# USB_to_UART.net
KiCad netlist of a schematic drawn in Altium Designer
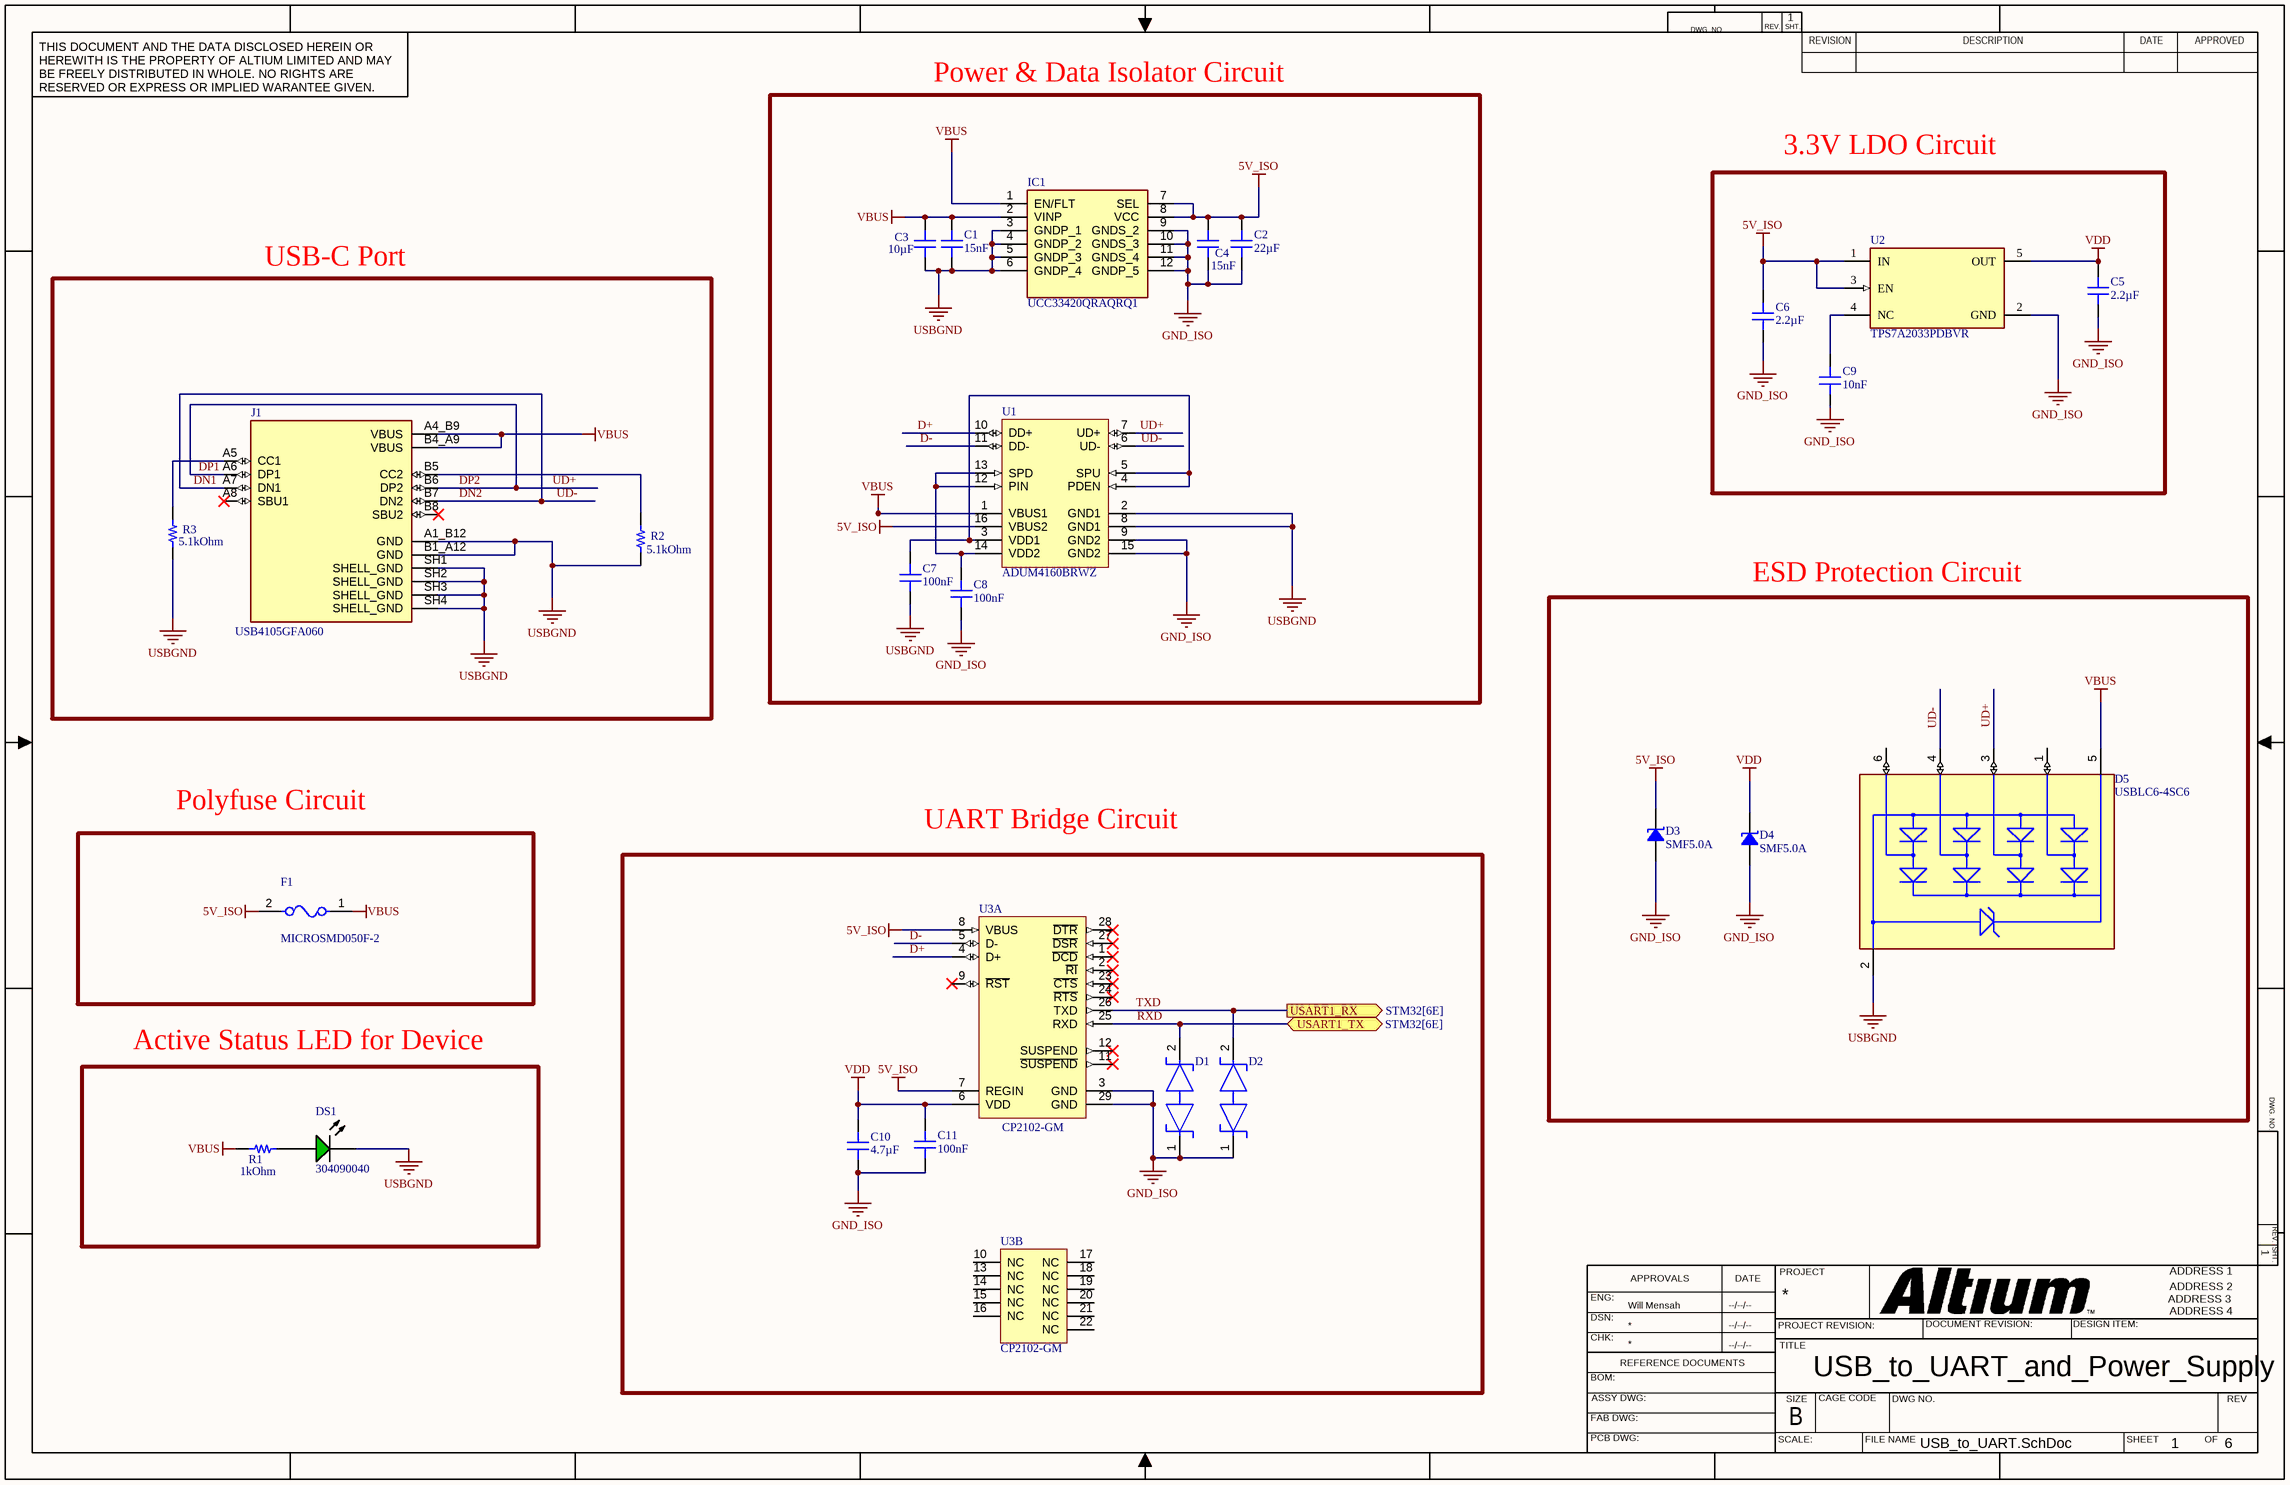
[diagram p0: USB_to_UART.SchDoc]

(export (version "E")
  (design (tool "Eeschema 10.0.6"))
  (components
    (comp (ref "C1")
      (value "15nF")
      (footprint "CAP 1206_3216 - 0.8MM")
      (description "CAP CER 15000PF 630V X7R 1206")
      (fields (field (name "PART NUMBER") "885342208013"))
      (libsource (lib "University of Massachusetts Lowell") (part "CAPACITOR"))
    )
    (comp (ref "C2")
      (value "22µF")
      (footprint "MURATA - GRM32E")
      (description "CAP CER 22UF 25V X7R 1210")
      (fields (field (name "PART NUMBER") "GRM32ER71E226ME15L"))
      (libsource (lib "University of Massachusetts Lowell") (part "CAPACITOR"))
    )
    (comp (ref "C3")
      (value "10µF")
      (footprint "MURATA - GRM32E")
      (description "CAP CER 10UF 50V X7R 1210")
      (fields (field (name "PART NUMBER") "GRM32ER71H106MA12L"))
      (libsource (lib "University of Massachusetts Lowell") (part "CAPACITOR"))
    )
    (comp (ref "C4")
      (value "15nF")
      (footprint "CAP 1206_3216 - 0.8MM")
      (description "CAP CER 15000PF 630V X7R 1206")
      (fields (field (name "PART NUMBER") "885342208013"))
      (libsource (lib "University of Massachusetts Lowell") (part "CAPACITOR"))
    )
    (comp (ref "C5")
      (value "2.2µF")
      (footprint "MURATA CAP GCM31M 1206_3216")
      (description "CAP CER 2.2UF 100V X8L 1206")
      (fields (field (name "PART NUMBER") "GCM31CL8EL225KE07L"))
      (libsource (lib "University of Massachusetts Lowell") (part "CAPACITOR"))
    )
    (comp (ref "C6")
      (value "2.2µF")
      (footprint "MURATA CAP GCM31M 1206_3216")
      (description "CAP CER 2.2UF 100V X8L 1206")
      (fields (field (name "PART NUMBER") "GCM31CL8EL225KE07L"))
      (libsource (lib "University of Massachusetts Lowell") (part "CAPACITOR"))
    )
    (comp (ref "C7")
      (value "100nF")
      (footprint "MURATA CAP GCM31M 1206_3216")
      (description "CAP CER 0.1UF 50V C0G/NP0 1206")
      (fields (field (name "PART NUMBER") "GCM31C5C1H104FA16L"))
      (libsource (lib "University of Massachusetts Lowell") (part "CAPACITOR"))
    )
    (comp (ref "C8")
      (value "100nF")
      (footprint "MURATA CAP GCM31M 1206_3216")
      (description "CAP CER 0.1UF 50V C0G/NP0 1206")
      (fields (field (name "PART NUMBER") "GCM31C5C1H104FA16L"))
      (libsource (lib "University of Massachusetts Lowell") (part "CAPACITOR"))
    )
    (comp (ref "C9")
      (value "10nF")
      (footprint "MURATA CAP GRM31B 1206_3216")
      (description "CAP CER 10000PF 250V U2J 1206")
      (fields (field (name "PART NUMBER") "GRM31B7U2E103JW31L"))
      (libsource (lib "University of Massachusetts Lowell") (part "CAPACITOR"))
    )
    (comp (ref "C10")
      (value "4.7µF")
      (footprint "MURATA GRM21B 0805_2012")
      (description "CAP CER 4.7UF 10V X7R 0805")
      (fields (field (name "PART NUMBER") "GRM21BR71A475KE51L"))
      (libsource (lib "University of Massachusetts Lowell") (part "CAPACITOR"))
    )
    (comp (ref "C11")
      (value "100nF")
      (footprint "MURATA CAP GCM31M 1206_3216")
      (description "CAP CER 0.1UF 50V C0G/NP0 1206")
      (fields (field (name "PART NUMBER") "GCM31C5C1H104FA16L"))
      (libsource (lib "University of Massachusetts Lowell") (part "CAPACITOR"))
    )
    (comp (ref "D1")
      (value "TPD1E10B06DPYR")
      (footprint "FP-DPY0002A-MFG")
      (description "TVS DIODE 5.5V 14V 2X1SON")
      (fields (field (name "MANUFACTURER") "Texas Instruments"))
      (libsource (lib "Altium Content Vault") (part "208e19b57522434895fa003e5d5b197"))
    )
    (comp (ref "D2")
      (value "TPD1E10B06DPYR")
      (footprint "FP-DPY0002A-MFG")
      (description "TVS DIODE 5.5V 14V 2X1SON")
      (fields (field (name "MANUFACTURER") "Texas Instruments"))
      (libsource (lib "Altium Content Vault") (part "208e19b57522434895fa003e5d5b197"))
    )
    (comp (ref "D3")
      (value "SMF5.0A")
      (footprint "SOD123F")
      (description "TVS SOD123FL 5V 200W UNIDIR")
      (libsource (lib "University of Massachusetts Lowell") (part "DIODE TVS UNI"))
    )
    (comp (ref "D4")
      (value "SMF5.0A")
      (footprint "SOD123F")
      (description "TVS SOD123FL 5V 200W UNIDIR")
      (libsource (lib "University of Massachusetts Lowell") (part "DIODE TVS UNI"))
    )
    (comp (ref "D5")
      (value "USBLC6-4SC6")
      (footprint "FP-SOT23-6L-MFG")
      (description "TVS DIODE 5.25V 17V SOT23-6")
      (fields
        (field (name "MANUFACTURER") "STMicroelectronics")
        (field (name "OCTOPART") "https://octopart.com/usblc6-4sc6-stmicroelectronics-347147")
      )
      (libsource (lib "Altium Content Vault") (part "3e70b616ccdc4c88b528e1820c4a7da"))
    )
    (comp (ref "DS1")
      (value "304090040")
      (footprint "LED-2P-2.28-3MM")
      (description "Green LED, 80 mW, 20 mA, -25 to 85 degC, 2-Pin THD")
      (fields (field (name "MANUFACTURER") "Shenzhen CGX"))
      (libsource (lib "University of Massachusetts Lowell") (part "LED-GREEN-AK-2"))
    )
    (comp (ref "F1")
      (value "MICROSMD050F-2")
      (footprint "FP-microSMD-MFG")
      (description "PTC RESET FUSE 13.2V 500MA 1210")
      (fields
        (field (name "MANUFACTURER") "Littelfuse")
        (field (name "OCTOPART") "https://octopart.com/microsmd050f-2-littelfuse-74214982")
      )
      (libsource (lib "Altium Content Vault") (part "5bcf9b9f640e542cf0359d10258e979"))
    )
    (comp (ref "IC1")
      (value "UCC33420QRAQRQ1")
      (footprint "SamacSys:UCC33020QRAQRQ1")
      (description "Integrated Circuit")
      (fields (field (name "MOUSER PART NUMBER") "595-UCC33420QRAQRQ1"))
      (libsource (lib "*") (part "UCC33420QRAQRQ1"))
    )
    (comp (ref "J1")
      (value "USB4105GFA060")
      (footprint "GCT_USB4105GFA060")
      (fields (field (name "MF") "Global Connector Technology"))
      (libsource (lib "University of Massachusetts Lowell") (part "USB4105GFA060"))
    )
    (comp (ref "R1")
      (value "1kOhm")
      (footprint "YAGEO RES 1206_3216")
      (description "RES 1K OHM 1% 1/4W 1206")
      (fields (field (name "PART NUMBER") "RC1206FR-101KL"))
      (libsource (lib "University of Massachusetts Lowell") (part "RESISTOR"))
    )
    (comp (ref "R2")
      (value "5.1kOhm")
      (footprint "YAGEO RES 1206_3216")
      (description "RES 5.1K OHM 0.1% 1/4W 1206")
      (fields (field (name "PART NUMBER") "RP1206BRD075K1L"))
      (libsource (lib "University of Massachusetts Lowell") (part "RESISTOR"))
    )
    (comp (ref "R3")
      (value "5.1kOhm")
      (footprint "YAGEO RES 1206_3216")
      (description "RES 5.1K OHM 0.1% 1/4W 1206")
      (fields (field (name "PART NUMBER") "RP1206BRD075K1L"))
      (libsource (lib "University of Massachusetts Lowell") (part "RESISTOR"))
    )
    (comp (ref "U1")
      (value "ADUM4160BRWZ")
      (footprint "RW-16_L")
      (fields (field (name "MANUFACTURER") "Analog Devices"))
      (libsource (lib "Altium Content Vault") (part "ADI-ADUM4160-16"))
    )
    (comp (ref "U2")
      (value "TPS7A2033PDBVR")
      (footprint "FP-DBV0005A-MFG")
      (description "IC REG LINEAR 3.3V 300MA SOT23-5")
      (libsource (lib "Altium Content Vault") (part "76aa7ad0ceb1012e0d85aeafc53095f"))
    )
    (comp (ref "U3")
      (value "CP2102-GM")
      (footprint "SLAB-QFN-28-3125x3125TP_N")
      (description "Single-Chip USB to UART Bridge, 1024 Bytes EEPROM, -40 to 85 degC, 28-pin QFN, Tube")
      (fields (field (name "MANUFACTURER") "Silicon Labs"))
      (libsource (lib "Altium Content Vault") (part "SLAB-CP210X-QFN-28-29"))
    )
  )
  (nets
    (net (code "1") (name "/D+") (class "Default")
      (node (ref "U1") (pin "10") (pinfunction "DD+_10") (pintype "bidirectional"))
      (node (ref "U3") (pin "4") (pinfunction "D+_4") (pintype "bidirectional"))
    )
    (net (code "2") (name "/D-") (class "Default")
      (node (ref "U1") (pin "11") (pinfunction "DD-_11") (pintype "bidirectional"))
      (node (ref "U3") (pin "5") (pinfunction "D-_5") (pintype "bidirectional"))
    )
    (net (code "3") (name "/DN1") (class "Default")
      (node (ref "D5") (pin "4") (pinfunction "I/O3_4") (pintype "bidirectional"))
      (node (ref "J1") (pin "A7") (pinfunction "DN1_A7") (pintype "bidirectional"))
      (node (ref "J1") (pin "B7") (pinfunction "DN2_B7") (pintype "bidirectional"))
      (node (ref "U1") (pin "6") (pinfunction "UD-_6") (pintype "bidirectional"))
    )
    (net (code "4") (name "/DP1") (class "Default")
      (node (ref "D5") (pin "3") (pinfunction "I/O2_3") (pintype "bidirectional"))
      (node (ref "J1") (pin "A6") (pinfunction "DP1_A6") (pintype "bidirectional"))
      (node (ref "J1") (pin "B6") (pinfunction "DP2_B6") (pintype "bidirectional"))
      (node (ref "U1") (pin "7") (pinfunction "UD+_7") (pintype "bidirectional"))
    )
    (net (code "5") (name "/RXD") (class "Default")
      (node (ref "D1") (pin "2") (pinfunction "2_2") (pintype "passive"))
      (node (ref "U3") (pin "25") (pinfunction "RXD_25") (pintype "input"))
    )
    (net (code "6") (name "/TXD") (class "Default")
      (node (ref "D2") (pin "2") (pinfunction "2_2") (pintype "passive"))
      (node (ref "U3") (pin "26") (pinfunction "TXD_26") (pintype "output"))
    )
    (net (code "7") (name "5V_ISO") (class "Default")
      (node (ref "C2") (pin "2") (pinfunction "2_2") (pintype "passive"))
      (node (ref "C4") (pin "2") (pinfunction "2_2") (pintype "passive"))
      (node (ref "C6") (pin "2") (pinfunction "2_2") (pintype "passive"))
      (node (ref "D3") (pin "2") (pinfunction "2_2") (pintype "passive"))
      (node (ref "F1") (pin "2") (pinfunction "2_2") (pintype "passive"))
      (node (ref "IC1") (pin "7") (pinfunction "SEL_7") (pintype "passive"))
      (node (ref "IC1") (pin "8") (pinfunction "VCC_8") (pintype "passive"))
      (node (ref "U1") (pin "16") (pinfunction "VBUS2_16") (pintype "power_in"))
      (node (ref "U2") (pin "1") (pinfunction "IN_1") (pintype "power_in"))
      (node (ref "U2") (pin "3") (pinfunction "EN_3") (pintype "input"))
      (node (ref "U3") (pin "7") (pinfunction "REGIN_7") (pintype "power_in"))
      (node (ref "U3") (pin "8") (pinfunction "VBUS_8") (pintype "input"))
    )
    (net (code "8") (name "GND_ISO") (class "Default")
      (node (ref "C10") (pin "1") (pinfunction "1_1") (pintype "passive"))
      (node (ref "C11") (pin "1") (pinfunction "1_1") (pintype "passive"))
      (node (ref "C2") (pin "1") (pinfunction "1_1") (pintype "passive"))
      (node (ref "C4") (pin "1") (pinfunction "1_1") (pintype "passive"))
      (node (ref "C5") (pin "1") (pinfunction "1_1") (pintype "passive"))
      (node (ref "C6") (pin "1") (pinfunction "1_1") (pintype "passive"))
      (node (ref "C8") (pin "1") (pinfunction "1_1") (pintype "passive"))
      (node (ref "C9") (pin "1") (pinfunction "1_1") (pintype "passive"))
      (node (ref "D1") (pin "1") (pinfunction "1_1") (pintype "passive"))
      (node (ref "D2") (pin "1") (pinfunction "1_1") (pintype "passive"))
      (node (ref "D3") (pin "1") (pinfunction "1_1") (pintype "passive"))
      (node (ref "D4") (pin "1") (pinfunction "1_1") (pintype "passive"))
      (node (ref "IC1") (pin "10") (pinfunction "GNDS_3_10") (pintype "passive"))
      (node (ref "IC1") (pin "11") (pinfunction "GNDS_4_11") (pintype "passive"))
      (node (ref "IC1") (pin "12") (pinfunction "GNDP_5_12") (pintype "passive"))
      (node (ref "IC1") (pin "9") (pinfunction "GNDS_2_9") (pintype "passive"))
      (node (ref "U1") (pin "15") (pinfunction "GND2_15") (pintype "power_in"))
      (node (ref "U1") (pin "9") (pinfunction "GND2_9") (pintype "power_in"))
      (node (ref "U2") (pin "2") (pinfunction "GND_2") (pintype "power_in"))
      (node (ref "U3") (pin "29") (pinfunction "GND_29") (pintype "power_in"))
      (node (ref "U3") (pin "3") (pinfunction "GND_3") (pintype "power_in"))
    )
    (net (code "9") (name "Net-(DS1-A)") (class "Default")
      (node (ref "DS1") (pin "1") (pinfunction "A_1") (pintype "passive"))
      (node (ref "R1") (pin "1") (pinfunction "1_1") (pintype "passive"))
    )
    (net (code "10") (name "Net-(J1-CC1)") (class "Default")
      (node (ref "J1") (pin "A5") (pinfunction "CC1_A5") (pintype "bidirectional"))
      (node (ref "R3") (pin "1") (pinfunction "1_1") (pintype "passive"))
    )
    (net (code "11") (name "Net-(J1-CC2)") (class "Default")
      (node (ref "J1") (pin "B5") (pinfunction "CC2_B5") (pintype "bidirectional"))
      (node (ref "R2") (pin "2") (pinfunction "2_2") (pintype "passive"))
    )
    (net (code "12") (name "Net-(U1-PDEN)") (class "Default")
      (node (ref "C7") (pin "2") (pinfunction "2_2") (pintype "passive"))
      (node (ref "U1") (pin "3") (pinfunction "VDD1_3") (pintype "power_in"))
      (node (ref "U1") (pin "4") (pinfunction "PDEN_4") (pintype "input"))
      (node (ref "U1") (pin "5") (pinfunction "SPU_5") (pintype "input"))
    )
    (net (code "13") (name "Net-(U1-PIN)") (class "Default")
      (node (ref "C8") (pin "2") (pinfunction "2_2") (pintype "passive"))
      (node (ref "U1") (pin "12") (pinfunction "PIN_12") (pintype "input"))
      (node (ref "U1") (pin "13") (pinfunction "SPD_13") (pintype "input"))
      (node (ref "U1") (pin "14") (pinfunction "VDD2_14") (pintype "power_in"))
    )
    (net (code "14") (name "Net-(U2-NC)") (class "Default")
      (node (ref "C9") (pin "2") (pinfunction "2_2") (pintype "passive"))
      (node (ref "U2") (pin "4") (pinfunction "NC_4") (pintype "passive"))
    )
    (net (code "15") (name "USBGND") (class "Default")
      (node (ref "C1") (pin "1") (pinfunction "1_1") (pintype "passive"))
      (node (ref "C3") (pin "1") (pinfunction "1_1") (pintype "passive"))
      (node (ref "C7") (pin "1") (pinfunction "1_1") (pintype "passive"))
      (node (ref "D5") (pin "2") (pinfunction "GND_2") (pintype "power_in"))
      (node (ref "DS1") (pin "2") (pinfunction "K_2") (pintype "passive"))
      (node (ref "IC1") (pin "3") (pinfunction "GNDP_1_3") (pintype "passive"))
      (node (ref "IC1") (pin "4") (pinfunction "GNDP_2_4") (pintype "passive"))
      (node (ref "IC1") (pin "5") (pinfunction "GNDP_3_5") (pintype "passive"))
      (node (ref "IC1") (pin "6") (pinfunction "GNDP_4_6") (pintype "passive"))
      (node (ref "J1") (pin "A1_B12") (pinfunction "GND_A1_B12") (pintype "power_in"))
      (node (ref "J1") (pin "B1_A12") (pinfunction "GND_B1_A12") (pintype "power_in"))
      (node (ref "J1") (pin "SH1") (pinfunction "SHELL_GND_SH1") (pintype "power_in"))
      (node (ref "J1") (pin "SH2") (pinfunction "SHELL_GND_SH2") (pintype "power_in"))
      (node (ref "J1") (pin "SH3") (pinfunction "SHELL_GND_SH3") (pintype "power_in"))
      (node (ref "J1") (pin "SH4") (pinfunction "SHELL_GND_SH4") (pintype "power_in"))
      (node (ref "R2") (pin "1") (pinfunction "1_1") (pintype "passive"))
      (node (ref "R3") (pin "2") (pinfunction "2_2") (pintype "passive"))
      (node (ref "U1") (pin "2") (pinfunction "GND1_2") (pintype "power_in"))
      (node (ref "U1") (pin "8") (pinfunction "GND1_8") (pintype "power_in"))
    )
    (net (code "16") (name "VBUS") (class "Default")
      (node (ref "C1") (pin "2") (pinfunction "2_2") (pintype "passive"))
      (node (ref "C3") (pin "2") (pinfunction "2_2") (pintype "passive"))
      (node (ref "D5") (pin "5") (pinfunction "VBUS_5") (pintype "power_in"))
      (node (ref "F1") (pin "1") (pinfunction "1_1") (pintype "passive"))
      (node (ref "IC1") (pin "1") (pinfunction "EN/FLT_1") (pintype "passive"))
      (node (ref "IC1") (pin "2") (pinfunction "VINP_2") (pintype "passive"))
      (node (ref "J1") (pin "A4_B9") (pinfunction "VBUS_A4_B9") (pintype "power_in"))
      (node (ref "J1") (pin "B4_A9") (pinfunction "VBUS_B4_A9") (pintype "power_in"))
      (node (ref "R1") (pin "2") (pinfunction "2_2") (pintype "passive"))
      (node (ref "U1") (pin "1") (pinfunction "VBUS1_1") (pintype "power_in"))
    )
    (net (code "17") (name "VDD") (class "Default")
      (node (ref "C10") (pin "2") (pinfunction "2_2") (pintype "passive"))
      (node (ref "C11") (pin "2") (pinfunction "2_2") (pintype "passive"))
      (node (ref "C5") (pin "2") (pinfunction "2_2") (pintype "passive"))
      (node (ref "D4") (pin "2") (pinfunction "2_2") (pintype "passive"))
      (node (ref "U2") (pin "5") (pinfunction "OUT_5") (pintype "passive"))
      (node (ref "U3") (pin "6") (pinfunction "VDD_6") (pintype "power_in"))
    )
    (net (code "18") (name "unconnected-(D5-I{slash}O1-Pad1)") (class "Default")
      (node (ref "D5") (pin "1") (pinfunction "I/O1_1") (pintype "bidirectional"))
    )
    (net (code "19") (name "unconnected-(D5-I{slash}O4-Pad6)") (class "Default")
      (node (ref "D5") (pin "6") (pinfunction "I/O4_6") (pintype "bidirectional"))
    )
    (net (code "20") (name "unconnected-(J1-SBU1-PadA8)") (class "Default")
      (node (ref "J1") (pin "A8") (pinfunction "SBU1_A8") (pintype "bidirectional+no_connect"))
    )
    (net (code "21") (name "unconnected-(J1-SBU2-PadB8)") (class "Default")
      (node (ref "J1") (pin "B8") (pinfunction "SBU2_B8") (pintype "bidirectional+no_connect"))
    )
    (net (code "22") (name "unconnected-(U3A-SUSPEND-Pad12)") (class "Default")
      (node (ref "U3") (pin "12") (pinfunction "SUSPEND_12") (pintype "output+no_connect"))
    )
    (net (code "23") (name "unconnected-(U3A-~{CTS}-Pad23)") (class "Default")
      (node (ref "U3") (pin "23") (pinfunction "~{CTS}_23") (pintype "input+no_connect"))
    )
    (net (code "24") (name "unconnected-(U3A-~{DCD}-Pad1)") (class "Default")
      (node (ref "U3") (pin "1") (pinfunction "~{DCD}_1") (pintype "input+no_connect"))
    )
    (net (code "25") (name "unconnected-(U3A-~{DSR}-Pad27)") (class "Default")
      (node (ref "U3") (pin "27") (pinfunction "~{DSR}_27") (pintype "input+no_connect"))
    )
    (net (code "26") (name "unconnected-(U3A-~{DTR}-Pad28)") (class "Default")
      (node (ref "U3") (pin "28") (pinfunction "~{DTR}_28") (pintype "output+no_connect"))
    )
    (net (code "27") (name "unconnected-(U3A-~{RI}-Pad2)") (class "Default")
      (node (ref "U3") (pin "2") (pinfunction "~{RI}_2") (pintype "input+no_connect"))
    )
    (net (code "28") (name "unconnected-(U3A-~{RST}-Pad9)") (class "Default")
      (node (ref "U3") (pin "9") (pinfunction "~{RST}_9") (pintype "bidirectional+no_connect"))
    )
    (net (code "29") (name "unconnected-(U3A-~{RTS}-Pad24)") (class "Default")
      (node (ref "U3") (pin "24") (pinfunction "~{RTS}_24") (pintype "output+no_connect"))
    )
    (net (code "30") (name "unconnected-(U3A-~{SUSPEND}-Pad11)") (class "Default")
      (node (ref "U3") (pin "11") (pinfunction "~{SUSPEND}_11") (pintype "output+no_connect"))
    )
    (net (code "31") (name "unconnected-(U3B-NC-Pad10)") (class "Default")
      (node (ref "U3") (pin "10") (pinfunction "NC_10") (pintype "passive"))
    )
    (net (code "32") (name "unconnected-(U3B-NC-Pad13)") (class "Default")
      (node (ref "U3") (pin "13") (pinfunction "NC_13") (pintype "passive"))
    )
    (net (code "33") (name "unconnected-(U3B-NC-Pad14)") (class "Default")
      (node (ref "U3") (pin "14") (pinfunction "NC_14") (pintype "passive"))
    )
    (net (code "34") (name "unconnected-(U3B-NC-Pad15)") (class "Default")
      (node (ref "U3") (pin "15") (pinfunction "NC_15") (pintype "passive"))
    )
    (net (code "35") (name "unconnected-(U3B-NC-Pad16)") (class "Default")
      (node (ref "U3") (pin "16") (pinfunction "NC_16") (pintype "passive"))
    )
    (net (code "36") (name "unconnected-(U3B-NC-Pad17)") (class "Default")
      (node (ref "U3") (pin "17") (pinfunction "NC_17") (pintype "passive"))
    )
    (net (code "37") (name "unconnected-(U3B-NC-Pad18)") (class "Default")
      (node (ref "U3") (pin "18") (pinfunction "NC_18") (pintype "passive"))
    )
    (net (code "38") (name "unconnected-(U3B-NC-Pad19)") (class "Default")
      (node (ref "U3") (pin "19") (pinfunction "NC_19") (pintype "passive"))
    )
    (net (code "39") (name "unconnected-(U3B-NC-Pad20)") (class "Default")
      (node (ref "U3") (pin "20") (pinfunction "NC_20") (pintype "passive"))
    )
    (net (code "40") (name "unconnected-(U3B-NC-Pad21)") (class "Default")
      (node (ref "U3") (pin "21") (pinfunction "NC_21") (pintype "passive"))
    )
    (net (code "41") (name "unconnected-(U3B-NC-Pad22)") (class "Default")
      (node (ref "U3") (pin "22") (pinfunction "NC_22") (pintype "passive"))
    )
  )
)
